# Cansat2019_1516_Payload_SectionA_v02.net
KiCad netlist of a schematic drawn in EAGLE
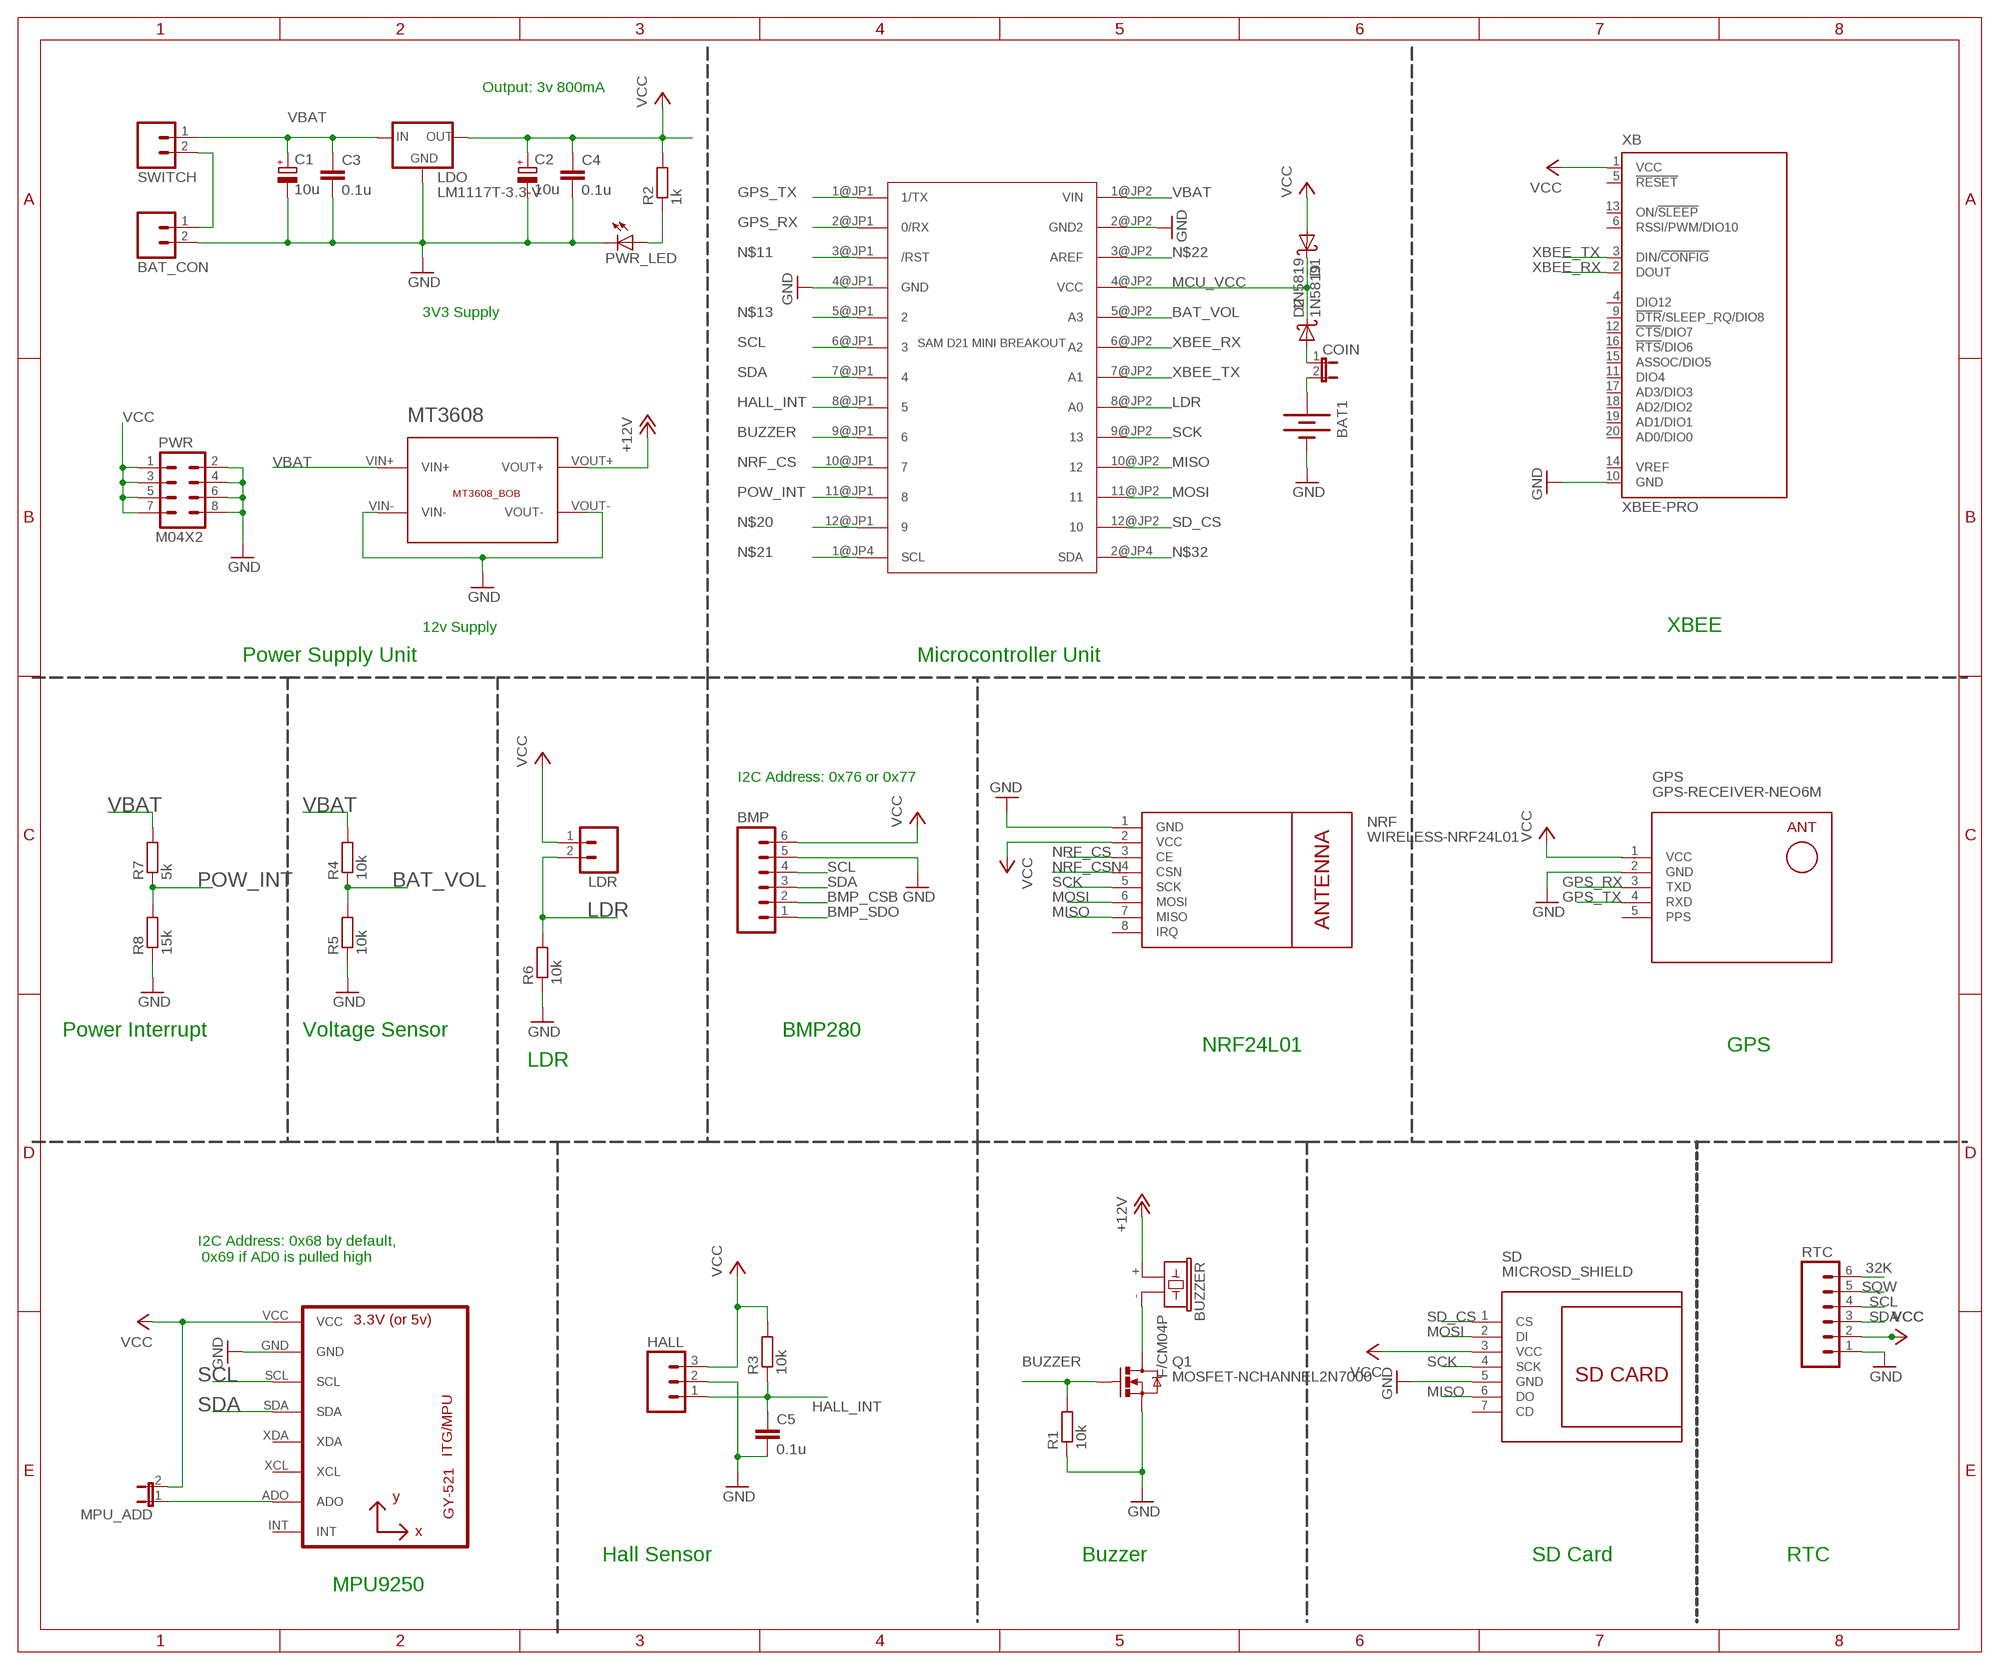
[diagram p0: schematic, sheet 1]

(export (version "E")
  (design (tool "Eeschema 10.0.6"))
  (components
    (comp (ref "BAT1")
      (value "BATTERY20PTH")
      (footprint "eagle-import:BATTCOM_20MM_PTH")
      (libsource (lib "eagle-import") (part "BATTERY20PTH"))
    )
    (comp (ref "BAT_CON")
      (value "M02")
      (footprint "eagle-import:02P")
      (libsource (lib "eagle-import") (part "M02"))
    )
    (comp (ref "BMP")
      (value "M06")
      (footprint "eagle-import:06P")
      (libsource (lib "eagle-import") (part "M06"))
    )
    (comp (ref "BUZZER")
      (value "F/CM04P")
      (footprint "eagle-import:F_CM04P")
      (libsource (lib "eagle-import") (part "F/CM04P"))
    )
    (comp (ref "C1")
      (value "10u")
      (footprint "eagle-import:E2,5-6")
      (libsource (lib "eagle-import") (part "CPOL-EUE2.5-6"))
    )
    (comp (ref "C2")
      (value "10u")
      (footprint "eagle-import:E2,5-6")
      (libsource (lib "eagle-import") (part "CPOL-EUE2.5-6"))
    )
    (comp (ref "C3")
      (value "0.1u")
      (footprint "eagle-import:C025-025X050")
      (libsource (lib "eagle-import") (part "C-EU025-025X050"))
    )
    (comp (ref "C4")
      (value "0.1u")
      (footprint "eagle-import:C025-025X050")
      (libsource (lib "eagle-import") (part "C-EU025-025X050"))
    )
    (comp (ref "C5")
      (value "0.1u")
      (footprint "eagle-import:C025-025X050")
      (libsource (lib "eagle-import") (part "C-EU025-025X050"))
    )
    (comp (ref "COIN")
      (value "JUMPER-2PTH")
      (footprint "eagle-import:1X02")
      (libsource (lib "eagle-import") (part "JUMPER-2PTH"))
    )
    (comp (ref "D1")
      (value "1N5819")
      (footprint "eagle-import:DO41-10")
      (libsource (lib "eagle-import") (part "1N5819"))
    )
    (comp (ref "D2")
      (value "1N5819")
      (footprint "eagle-import:DO41-10")
      (libsource (lib "eagle-import") (part "1N5819"))
    )
    (comp (ref "GPS")
      (value "GPS-RECEIVER-NEO6M")
      (footprint "eagle-import:GPS-RECEIVER-NEO6M")
      (libsource (lib "eagle-import") (part "GPS-RECEIVER-NEO6M"))
    )
    (comp (ref "HALL")
      (value "M03")
      (footprint "eagle-import:03P")
      (libsource (lib "eagle-import") (part "M03"))
    )
    (comp (ref "LDO")
      (value "LM1117T-3.3-V")
      (footprint "eagle-import:TO220V")
      (libsource (lib "eagle-import") (part "LM1117T--V3.3"))
    )
    (comp (ref "LDR")
      (value "M02")
      (footprint "eagle-import:02P")
      (libsource (lib "eagle-import") (part "M02"))
    )
    (comp (ref "MPU")
      (value "GY-521MPU6050")
      (footprint "eagle-import:GY-521")
      (libsource (lib "eagle-import") (part "GY-521MPU6050"))
    )
    (comp (ref "MPU_ADD")
      (value "JUMPER-2PTH")
      (footprint "eagle-import:1X02")
      (libsource (lib "eagle-import") (part "JUMPER-2PTH"))
    )
    (comp (ref "MT3608")
      (value "MT3608_BOB")
      (footprint "eagle-import:MT3608_BOB")
      (libsource (lib "eagle-import") (part "MT3608_BOB"))
    )
    (comp (ref "NRF")
      (value "WIRELESS-NRF24L01")
      (footprint "eagle-import:WIRELESS-NRF24L01")
      (libsource (lib "eagle-import") (part "WIRELESS-NRF24L01"))
    )
    (comp (ref "PWR")
      (value "M04X2")
      (footprint "eagle-import:2X4")
      (libsource (lib "eagle-import") (part "M04X2"))
    )
    (comp (ref "PWR_LED")
      (value "LED3MM")
      (footprint "eagle-import:LED3MM")
      (libsource (lib "eagle-import") (part "LED3MM"))
    )
    (comp (ref "Q1")
      (value "MOSFET-NCHANNEL2N7000")
      (footprint "eagle-import:TO-92")
      (libsource (lib "eagle-import") (part "MOSFET-NCHANNEL2N7000"))
    )
    (comp (ref "R1")
      (value "10k")
      (footprint "eagle-import:0204_7")
      (libsource (lib "eagle-import") (part "R-EU_0204/7"))
    )
    (comp (ref "R2")
      (value "1k")
      (footprint "eagle-import:0204_7")
      (libsource (lib "eagle-import") (part "R-EU_0204/7"))
    )
    (comp (ref "R3")
      (value "10k")
      (footprint "eagle-import:0204_7")
      (libsource (lib "eagle-import") (part "R-EU_0204/7"))
    )
    (comp (ref "R4")
      (value "10k")
      (footprint "eagle-import:0204_7")
      (libsource (lib "eagle-import") (part "R-EU_0204/7"))
    )
    (comp (ref "R5")
      (value "10k")
      (footprint "eagle-import:0204_7")
      (libsource (lib "eagle-import") (part "R-EU_0204/7"))
    )
    (comp (ref "R6")
      (value "10k")
      (footprint "eagle-import:0204_7")
      (libsource (lib "eagle-import") (part "R-EU_0204/7"))
    )
    (comp (ref "R7")
      (value "5k")
      (footprint "eagle-import:0204_7")
      (libsource (lib "eagle-import") (part "R-EU_0204/7"))
    )
    (comp (ref "R8")
      (value "15k")
      (footprint "eagle-import:0204_7")
      (libsource (lib "eagle-import") (part "R-EU_0204/7"))
    )
    (comp (ref "RTC")
      (value "M06")
      (footprint "eagle-import:06P")
      (libsource (lib "eagle-import") (part "M06"))
    )
    (comp (ref "SAMD")
      (value "SAM_D21_MINI_BREAKOUT")
      (footprint "eagle-import:JP1_SPARKFUN-SAMD21-MINI-BREAKOUT-V10")
      (libsource (lib "eagle-import") (part "SAM_D21_MINI_BREAKOUT"))
    )
    (comp (ref "SD")
      (value "MICROSD_SHIELD")
      (footprint "eagle-import:MICROSD_SHIELD")
      (libsource (lib "eagle-import") (part "MICROSD_SHIELD"))
    )
    (comp (ref "SWITCH")
      (value "M02")
      (footprint "eagle-import:02P")
      (libsource (lib "eagle-import") (part "M02"))
    )
    (comp (ref "XB")
      (value "XBEE-PRO")
      (footprint "eagle-import:XBEE-PRO")
      (fields (field (name "MPN") "XBP24-AWI-001"))
      (libsource (lib "eagle-import") (part "XBEE-PRO"))
    )
  )
  (nets
    (net (code "1") (name "+12V") (class "Default")
      (node (ref "BUZZER") (pin "+") (pinfunction "1_+") (pintype "passive"))
      (node (ref "MT3608") (pin "VOUT+") (pinfunction "VOUT+_VOUT+") (pintype "bidirectional"))
    )
    (net (code "2") (name "/32K") (class "Default")
      (node (ref "RTC") (pin "6") (pinfunction "6_6") (pintype "passive"))
    )
    (net (code "3") (name "/BAT_VOL") (class "Default")
      (node (ref "R4") (pin "1") (pinfunction "1_1") (pintype "passive"))
      (node (ref "R5") (pin "2") (pinfunction "2_2") (pintype "passive"))
      (node (ref "SAMD") (pin "5@JP2") (pinfunction "A3_5@JP2") (pintype "bidirectional"))
    )
    (net (code "4") (name "/BMP_CSB") (class "Default")
      (node (ref "BMP") (pin "2") (pinfunction "2_2") (pintype "passive"))
    )
    (net (code "5") (name "/BMP_SDO") (class "Default")
      (node (ref "BMP") (pin "1") (pinfunction "1_1") (pintype "passive"))
    )
    (net (code "6") (name "/BUZZER") (class "Default")
      (node (ref "Q1") (pin "2") (pinfunction "G_2") (pintype "passive"))
      (node (ref "R1") (pin "2") (pinfunction "2_2") (pintype "passive"))
      (node (ref "SAMD") (pin "9@JP1") (pinfunction "6_9@JP1") (pintype "bidirectional"))
    )
    (net (code "7") (name "/GPS_RX") (class "Default")
      (node (ref "GPS") (pin "3") (pinfunction "TXD_3") (pintype "bidirectional"))
      (node (ref "SAMD") (pin "2@JP1") (pinfunction "0/RX_2@JP1") (pintype "bidirectional"))
    )
    (net (code "8") (name "/GPS_TX") (class "Default")
      (node (ref "GPS") (pin "4") (pinfunction "RXD_4") (pintype "power_in"))
      (node (ref "SAMD") (pin "1@JP1") (pinfunction "1/TX_1@JP1") (pintype "bidirectional"))
    )
    (net (code "9") (name "/HALL_INT") (class "Default")
      (node (ref "C5") (pin "1") (pinfunction "1_1") (pintype "passive"))
      (node (ref "HALL") (pin "1") (pinfunction "1_1") (pintype "passive"))
      (node (ref "R3") (pin "1") (pinfunction "1_1") (pintype "passive"))
      (node (ref "SAMD") (pin "8@JP1") (pinfunction "5_8@JP1") (pintype "bidirectional"))
    )
    (net (code "10") (name "/LDR") (class "Default")
      (node (ref "LDR") (pin "2") (pinfunction "2_2") (pintype "passive"))
      (node (ref "R6") (pin "2") (pinfunction "2_2") (pintype "passive"))
      (node (ref "SAMD") (pin "8@JP2") (pinfunction "A0_8@JP2") (pintype "bidirectional"))
    )
    (net (code "11") (name "/MCU_VCC") (class "Default")
      (node (ref "D1") (pin "C") (pinfunction "C_C") (pintype "passive"))
      (node (ref "D2") (pin "C") (pinfunction "C_C") (pintype "passive"))
      (node (ref "SAMD") (pin "4@JP2") (pinfunction "VCC_4@JP2") (pintype "power_in"))
    )
    (net (code "12") (name "/MISO") (class "Default")
      (node (ref "NRF") (pin "7") (pinfunction "MISO_7") (pintype "bidirectional"))
      (node (ref "SAMD") (pin "10@JP2") (pinfunction "12_10@JP2") (pintype "bidirectional"))
      (node (ref "SD") (pin "6") (pinfunction "DO_6") (pintype "bidirectional"))
    )
    (net (code "13") (name "/MOSI") (class "Default")
      (node (ref "NRF") (pin "6") (pinfunction "MOSI_6") (pintype "bidirectional"))
      (node (ref "SAMD") (pin "11@JP2") (pinfunction "11_11@JP2") (pintype "bidirectional"))
      (node (ref "SD") (pin "2") (pinfunction "DI_2") (pintype "bidirectional"))
    )
    (net (code "14") (name "/N$11") (class "Default")
      (node (ref "SAMD") (pin "3@JP1") (pinfunction "/RST_3@JP1") (pintype "input"))
    )
    (net (code "15") (name "/N$13") (class "Default")
      (node (ref "SAMD") (pin "5@JP1") (pinfunction "2_5@JP1") (pintype "bidirectional"))
    )
    (net (code "16") (name "/N$20") (class "Default")
      (node (ref "SAMD") (pin "12@JP1") (pinfunction "9_12@JP1") (pintype "bidirectional"))
    )
    (net (code "17") (name "/N$21") (class "Default")
      (node (ref "SAMD") (pin "1@JP4") (pinfunction "SCL_1@JP4") (pintype "bidirectional"))
    )
    (net (code "18") (name "/N$22") (class "Default")
      (node (ref "SAMD") (pin "3@JP2") (pinfunction "AREF_3@JP2") (pintype "power_in"))
    )
    (net (code "19") (name "/N$32") (class "Default")
      (node (ref "SAMD") (pin "2@JP4") (pinfunction "SDA_2@JP4") (pintype "bidirectional"))
    )
    (net (code "20") (name "/NRF_CS") (class "Default")
      (node (ref "NRF") (pin "3") (pinfunction "CE_3") (pintype "bidirectional"))
      (node (ref "SAMD") (pin "10@JP1") (pinfunction "7_10@JP1") (pintype "bidirectional"))
    )
    (net (code "21") (name "/NRF_CSN") (class "Default")
      (node (ref "NRF") (pin "4") (pinfunction "CSN_4") (pintype "bidirectional"))
    )
    (net (code "22") (name "/POW_INT") (class "Default")
      (node (ref "R7") (pin "1") (pinfunction "1_1") (pintype "passive"))
      (node (ref "R8") (pin "2") (pinfunction "2_2") (pintype "passive"))
      (node (ref "SAMD") (pin "11@JP1") (pinfunction "8_11@JP1") (pintype "bidirectional"))
    )
    (net (code "23") (name "/PPS") (class "Default")
      (node (ref "GPS") (pin "5") (pinfunction "PPS_5") (pintype "power_in"))
    )
    (net (code "24") (name "/SCK") (class "Default")
      (node (ref "NRF") (pin "5") (pinfunction "SCK_5") (pintype "bidirectional"))
      (node (ref "SAMD") (pin "9@JP2") (pinfunction "13_9@JP2") (pintype "bidirectional"))
      (node (ref "SD") (pin "4") (pinfunction "SCK_4") (pintype "bidirectional"))
    )
    (net (code "25") (name "/SCL") (class "Default")
      (node (ref "BMP") (pin "4") (pinfunction "4_4") (pintype "passive"))
      (node (ref "MPU") (pin "SCL") (pinfunction "SCL_SCL") (pintype "bidirectional"))
      (node (ref "RTC") (pin "4") (pinfunction "4_4") (pintype "passive"))
      (node (ref "SAMD") (pin "6@JP1") (pinfunction "3_6@JP1") (pintype "bidirectional"))
    )
    (net (code "26") (name "/SDA") (class "Default")
      (node (ref "BMP") (pin "3") (pinfunction "3_3") (pintype "passive"))
      (node (ref "MPU") (pin "SDA") (pinfunction "SDA_SDA") (pintype "bidirectional"))
      (node (ref "RTC") (pin "3") (pinfunction "3_3") (pintype "passive"))
      (node (ref "SAMD") (pin "7@JP1") (pinfunction "4_7@JP1") (pintype "bidirectional"))
    )
    (net (code "27") (name "/SD_CS") (class "Default")
      (node (ref "SAMD") (pin "12@JP2") (pinfunction "10_12@JP2") (pintype "bidirectional"))
      (node (ref "SD") (pin "1") (pinfunction "CS_1") (pintype "bidirectional"))
    )
    (net (code "28") (name "/SQW") (class "Default")
      (node (ref "RTC") (pin "5") (pinfunction "5_5") (pintype "passive"))
    )
    (net (code "29") (name "/VBAT") (class "Default")
      (node (ref "C1") (pin "+") (pinfunction "+_+") (pintype "passive"))
      (node (ref "C3") (pin "1") (pinfunction "1_1") (pintype "passive"))
      (node (ref "LDO") (pin "3") (pinfunction "IN_3") (pintype "input"))
      (node (ref "MT3608") (pin "VIN+") (pinfunction "VIN+_VIN+") (pintype "bidirectional"))
      (node (ref "R4") (pin "2") (pinfunction "2_2") (pintype "passive"))
      (node (ref "R7") (pin "2") (pinfunction "2_2") (pintype "passive"))
      (node (ref "SAMD") (pin "1@JP2") (pinfunction "VIN_1@JP2") (pintype "power_in"))
      (node (ref "SWITCH") (pin "1") (pinfunction "1_1") (pintype "passive"))
    )
    (net (code "30") (name "/XBEE_RX") (class "Default")
      (node (ref "SAMD") (pin "6@JP2") (pinfunction "A2_6@JP2") (pintype "bidirectional"))
      (node (ref "XB") (pin "2") (pinfunction "DOUT_2") (pintype "output"))
    )
    (net (code "31") (name "/XBEE_TX") (class "Default")
      (node (ref "SAMD") (pin "7@JP2") (pinfunction "A1_7@JP2") (pintype "bidirectional"))
      (node (ref "XB") (pin "3") (pinfunction "DIN/~{CONFIG}_3") (pintype "input"))
    )
    (net (code "32") (name "GND") (class "Default")
      (node (ref "BAT1") (pin "2") (pinfunction "-_2") (pintype "power_in"))
      (node (ref "BAT_CON") (pin "2") (pinfunction "2_2") (pintype "passive"))
      (node (ref "BMP") (pin "5") (pinfunction "5_5") (pintype "passive"))
      (node (ref "C1") (pin "-") (pinfunction "-_-") (pintype "passive"))
      (node (ref "C2") (pin "-") (pinfunction "-_-") (pintype "passive"))
      (node (ref "C3") (pin "2") (pinfunction "2_2") (pintype "passive"))
      (node (ref "C4") (pin "2") (pinfunction "2_2") (pintype "passive"))
      (node (ref "C5") (pin "2") (pinfunction "2_2") (pintype "passive"))
      (node (ref "GPS") (pin "2") (pinfunction "GND_2") (pintype "bidirectional"))
      (node (ref "HALL") (pin "2") (pinfunction "2_2") (pintype "passive"))
      (node (ref "LDO") (pin "1") (pinfunction "GND_1") (pintype "input"))
      (node (ref "MPU") (pin "GND") (pinfunction "GND_GND") (pintype "bidirectional"))
      (node (ref "MT3608") (pin "VIN-") (pinfunction "VIN-_VIN-") (pintype "bidirectional"))
      (node (ref "MT3608") (pin "VOUT-") (pinfunction "VOUT-_VOUT-") (pintype "bidirectional"))
      (node (ref "NRF") (pin "1") (pinfunction "GND_1") (pintype "power_in"))
      (node (ref "PWR") (pin "2") (pinfunction "2_2") (pintype "passive"))
      (node (ref "PWR") (pin "4") (pinfunction "4_4") (pintype "passive"))
      (node (ref "PWR") (pin "6") (pinfunction "6_6") (pintype "passive"))
      (node (ref "PWR") (pin "8") (pinfunction "8_8") (pintype "passive"))
      (node (ref "PWR_LED") (pin "K") (pinfunction "C_K") (pintype "passive"))
      (node (ref "Q1") (pin "1") (pinfunction "S_1") (pintype "passive"))
      (node (ref "R1") (pin "1") (pinfunction "1_1") (pintype "passive"))
      (node (ref "R5") (pin "1") (pinfunction "1_1") (pintype "passive"))
      (node (ref "R6") (pin "1") (pinfunction "1_1") (pintype "passive"))
      (node (ref "R8") (pin "1") (pinfunction "1_1") (pintype "passive"))
      (node (ref "RTC") (pin "1") (pinfunction "1_1") (pintype "passive"))
      (node (ref "SAMD") (pin "2@JP2") (pinfunction "GND2_2@JP2") (pintype "power_in"))
      (node (ref "SAMD") (pin "4@JP1") (pinfunction "GND_4@JP1") (pintype "power_in"))
      (node (ref "SD") (pin "5") (pinfunction "GND_5") (pintype "power_in"))
      (node (ref "XB") (pin "10") (pinfunction "GND_10") (pintype "power_in"))
    )
    (net (code "33") (name "Net-(BAT1-+)") (class "Default")
      (node (ref "BAT1") (pin "1") (pinfunction "+_1") (pintype "power_in"))
      (node (ref "COIN") (pin "2") (pinfunction "2_2") (pintype "passive"))
    )
    (net (code "34") (name "Net-(BAT_CON-Pad1)") (class "Default")
      (node (ref "BAT_CON") (pin "1") (pinfunction "1_1") (pintype "passive"))
      (node (ref "SWITCH") (pin "2") (pinfunction "2_2") (pintype "passive"))
    )
    (net (code "35") (name "Net-(BUZZER-2)") (class "Default")
      (node (ref "BUZZER") (pin "-") (pinfunction "2_-") (pintype "passive"))
      (node (ref "Q1") (pin "3") (pinfunction "D_3") (pintype "passive"))
    )
    (net (code "36") (name "Net-(COIN-Pad1)") (class "Default")
      (node (ref "COIN") (pin "1") (pinfunction "1_1") (pintype "passive"))
      (node (ref "D2") (pin "A") (pinfunction "A_A") (pintype "passive"))
    )
    (net (code "37") (name "Net-(MPU-PadADO)") (class "Default")
      (node (ref "MPU") (pin "ADO") (pinfunction "ADO_ADO") (pintype "bidirectional"))
      (node (ref "MPU_ADD") (pin "1") (pinfunction "1_1") (pintype "passive"))
    )
    (net (code "38") (name "Net-(PWR_LED-PadA)") (class "Default")
      (node (ref "PWR_LED") (pin "A") (pinfunction "A_A") (pintype "passive"))
      (node (ref "R2") (pin "1") (pinfunction "1_1") (pintype "passive"))
    )
    (net (code "39") (name "VCC") (class "Default")
      (node (ref "BMP") (pin "6") (pinfunction "6_6") (pintype "passive"))
      (node (ref "C2") (pin "+") (pinfunction "+_+") (pintype "passive"))
      (node (ref "C4") (pin "1") (pinfunction "1_1") (pintype "passive"))
      (node (ref "D1") (pin "A") (pinfunction "A_A") (pintype "passive"))
      (node (ref "GPS") (pin "1") (pinfunction "VCC_1") (pintype "bidirectional"))
      (node (ref "HALL") (pin "3") (pinfunction "3_3") (pintype "passive"))
      (node (ref "LDO") (pin "2") (pinfunction "OUT_2") (pintype "passive"))
      (node (ref "LDR") (pin "1") (pinfunction "1_1") (pintype "passive"))
      (node (ref "MPU") (pin "VCC") (pinfunction "VCC_VCC") (pintype "bidirectional"))
      (node (ref "MPU_ADD") (pin "2") (pinfunction "2_2") (pintype "passive"))
      (node (ref "NRF") (pin "2") (pinfunction "VCC_2") (pintype "power_in"))
      (node (ref "PWR") (pin "1") (pinfunction "1_1") (pintype "passive"))
      (node (ref "PWR") (pin "3") (pinfunction "3_3") (pintype "passive"))
      (node (ref "PWR") (pin "5") (pinfunction "5_5") (pintype "passive"))
      (node (ref "PWR") (pin "7") (pinfunction "7_7") (pintype "passive"))
      (node (ref "R2") (pin "2") (pinfunction "2_2") (pintype "passive"))
      (node (ref "R3") (pin "2") (pinfunction "2_2") (pintype "passive"))
      (node (ref "RTC") (pin "2") (pinfunction "2_2") (pintype "passive"))
      (node (ref "SD") (pin "3") (pinfunction "VCC_3") (pintype "power_in"))
      (node (ref "XB") (pin "1") (pinfunction "VCC_1") (pintype "power_in"))
    )
    (net (code "40") (name "unconnected-(MPU-PadINT)") (class "Default")
      (node (ref "MPU") (pin "INT") (pinfunction "INT_INT") (pintype "bidirectional"))
    )
    (net (code "41") (name "unconnected-(MPU-PadXCL)") (class "Default")
      (node (ref "MPU") (pin "XCL") (pinfunction "XCL_XCL") (pintype "bidirectional"))
    )
    (net (code "42") (name "unconnected-(MPU-PadXDA)") (class "Default")
      (node (ref "MPU") (pin "XDA") (pinfunction "XDA_XDA") (pintype "bidirectional"))
    )
    (net (code "43") (name "unconnected-(NRF-IRQ-Pad8)") (class "Default")
      (node (ref "NRF") (pin "8") (pinfunction "IRQ_8") (pintype "bidirectional"))
    )
    (net (code "44") (name "unconnected-(SD-CD-Pad7)") (class "Default")
      (node (ref "SD") (pin "7") (pinfunction "CD_7") (pintype "bidirectional"))
    )
    (net (code "45") (name "unconnected-(XB-AD0{slash}DIO0-Pad20)") (class "Default")
      (node (ref "XB") (pin "20") (pinfunction "AD0/DIO0_20") (pintype "bidirectional"))
    )
    (net (code "46") (name "unconnected-(XB-AD1{slash}DIO1-Pad19)") (class "Default")
      (node (ref "XB") (pin "19") (pinfunction "AD1/DIO1_19") (pintype "bidirectional"))
    )
    (net (code "47") (name "unconnected-(XB-AD2{slash}DIO2-Pad18)") (class "Default")
      (node (ref "XB") (pin "18") (pinfunction "AD2/DIO2_18") (pintype "bidirectional"))
    )
    (net (code "48") (name "unconnected-(XB-AD3{slash}DIO3-Pad17)") (class "Default")
      (node (ref "XB") (pin "17") (pinfunction "AD3/DIO3_17") (pintype "bidirectional"))
    )
    (net (code "49") (name "unconnected-(XB-ASSOC{slash}DIO5-Pad15)") (class "Default")
      (node (ref "XB") (pin "15") (pinfunction "ASSOC/DIO5_15") (pintype "bidirectional"))
    )
    (net (code "50") (name "unconnected-(XB-DIO4-Pad11)") (class "Default")
      (node (ref "XB") (pin "11") (pinfunction "DIO4_11") (pintype "bidirectional"))
    )
    (net (code "51") (name "unconnected-(XB-DIO12-Pad4)") (class "Default")
      (node (ref "XB") (pin "4") (pinfunction "DIO12_4") (pintype "bidirectional"))
    )
    (net (code "52") (name "unconnected-(XB-ON{slash}~{SLEEP}-Pad13)") (class "Default")
      (node (ref "XB") (pin "13") (pinfunction "ON/~{SLEEP}_13") (pintype "output"))
    )
    (net (code "53") (name "unconnected-(XB-RSSI{slash}PWM{slash}DIO10-Pad6)") (class "Default")
      (node (ref "XB") (pin "6") (pinfunction "RSSI/PWM/DIO10_6") (pintype "output"))
    )
    (net (code "54") (name "unconnected-(XB-VREF-Pad14)") (class "Default")
      (node (ref "XB") (pin "14") (pinfunction "VREF_14") (pintype "input"))
    )
    (net (code "55") (name "unconnected-(XB-~{CTS}{slash}DIO7-Pad12)") (class "Default")
      (node (ref "XB") (pin "12") (pinfunction "~{CTS}/DIO7_12") (pintype "bidirectional"))
    )
    (net (code "56") (name "unconnected-(XB-~{DTR}{slash}SLEEP_RQ{slash}DIO8-Pad9)") (class "Default")
      (node (ref "XB") (pin "9") (pinfunction "~{DTR}/SLEEP_RQ/DIO8_9") (pintype "bidirectional"))
    )
    (net (code "57") (name "unconnected-(XB-~{RESET}-Pad5)") (class "Default")
      (node (ref "XB") (pin "5") (pinfunction "~{RESET}_5") (pintype "input"))
    )
    (net (code "58") (name "unconnected-(XB-~{RTS}{slash}DIO6-Pad16)") (class "Default")
      (node (ref "XB") (pin "16") (pinfunction "~{RTS}/DIO6_16") (pintype "bidirectional"))
    )
  )
)
